# DCO.net
KiCad netlist of a schematic drawn in EAGLE
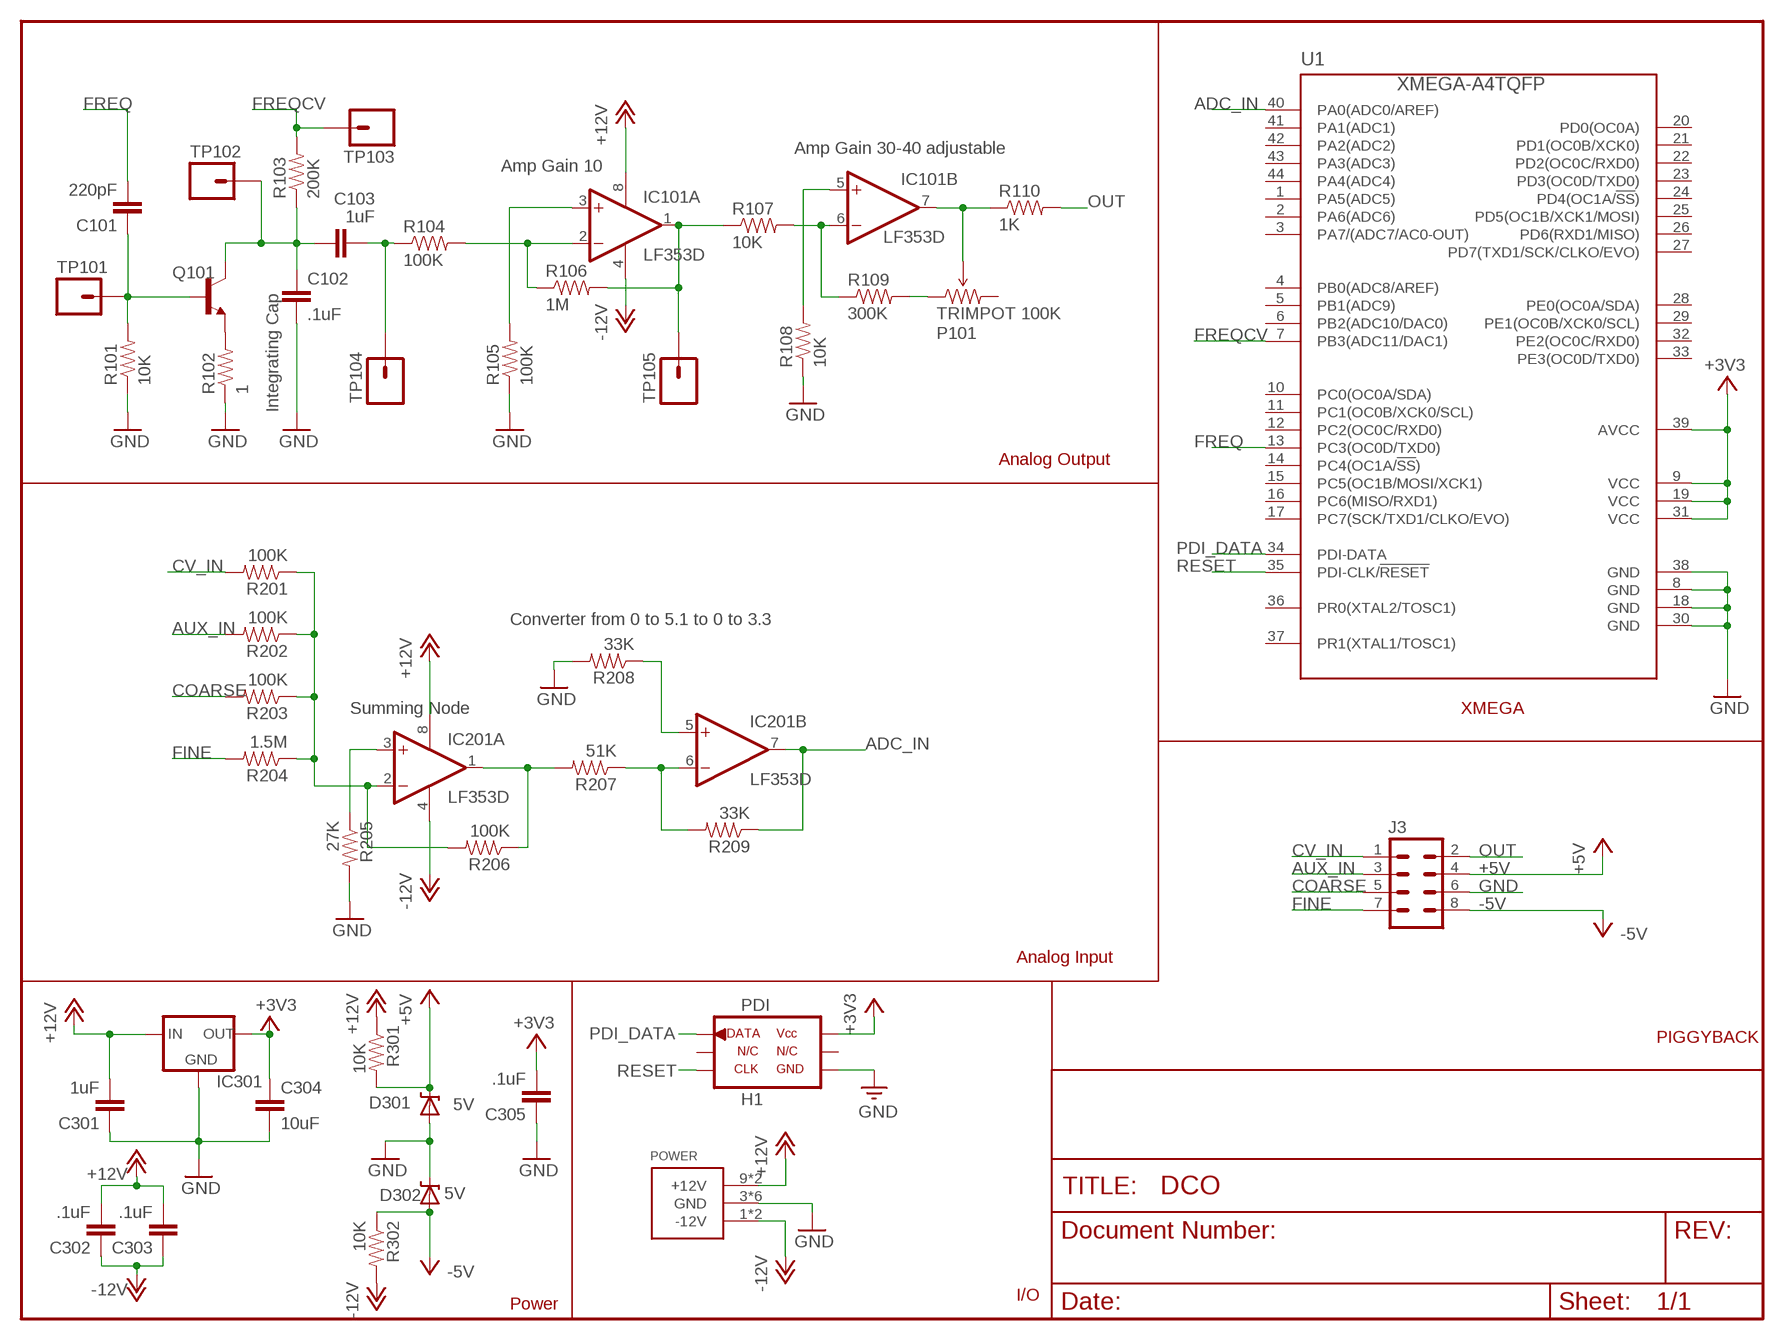
[diagram p0: schematic, sheet 1]

(export (version "E")
  (design (tool "Eeschema 10.0.6"))
  (components
    (comp (ref "C101")
      (value "220pF")
      (footprint "eagle-import:0603-CAP")
      (libsource (lib "eagle-import") (part "CAP0603-CAP"))
    )
    (comp (ref "C102")
      (value ".1uF")
      (footprint "eagle-import:1210")
      (libsource (lib "eagle-import") (part "CAP1210"))
    )
    (comp (ref "C103")
      (value "1uF")
      (footprint "eagle-import:0805")
      (libsource (lib "eagle-import") (part "CAP0805"))
    )
    (comp (ref "C301")
      (value "1uF")
      (footprint "eagle-import:0805")
      (libsource (lib "eagle-import") (part "CAP0805"))
    )
    (comp (ref "C302")
      (value ".1uF")
      (footprint "eagle-import:0603-CAP")
      (libsource (lib "eagle-import") (part "CAP0603-CAP"))
    )
    (comp (ref "C303")
      (value ".1uF")
      (footprint "eagle-import:0603-CAP")
      (libsource (lib "eagle-import") (part "CAP0603-CAP"))
    )
    (comp (ref "C304")
      (value "10uF")
      (footprint "eagle-import:1206")
      (libsource (lib "eagle-import") (part "CAP1206"))
    )
    (comp (ref "C305")
      (value ".1uF")
      (footprint "eagle-import:0603-CAP")
      (libsource (lib "eagle-import") (part "CAP0603-CAP"))
    )
    (comp (ref "D301")
      (value "5V")
      (footprint "eagle-import:SOD-323")
      (libsource (lib "eagle-import") (part "DIODE-ZENER-BZT52"))
    )
    (comp (ref "D302")
      (value "5V")
      (footprint "eagle-import:SOD-323")
      (libsource (lib "eagle-import") (part "DIODE-ZENER-BZT52"))
    )
    (comp (ref "H1")
      (value "PDI")
      (footprint "eagle-import:AVR_ISP_6")
      (libsource (lib "eagle-import") (part "AVR_PDI_6"))
    )
    (comp (ref "IC101")
      (value "LF353D")
      (footprint "eagle-import:SO08")
      (libsource (lib "eagle-import") (part "LF353D"))
    )
    (comp (ref "IC201")
      (value "LF353D")
      (footprint "eagle-import:SO08")
      (libsource (lib "eagle-import") (part "LF353D"))
    )
    (comp (ref "IC301")
      (value "V_REG_MIC2920")
      (footprint "eagle-import:SOT223")
      (libsource (lib "eagle-import") (part "V_REG_MIC2920"))
    )
    (comp (ref "J3")
      (value "M04X2")
      (footprint "eagle-import:2X4")
      (libsource (lib "eagle-import") (part "M04X2"))
    )
    (comp (ref "P101")
      (value "TRIMPOT 100K")
      (footprint "eagle-import:TRIM_POT_PTH")
      (libsource (lib "eagle-import") (part "TRIMPOTPTH"))
    )
    (comp (ref "POWER")
      (value "POWER_SIMPLE16")
      (footprint "eagle-import:POWER_16")
      (libsource (lib "eagle-import") (part "POWER_SIMPLE16"))
    )
    (comp (ref "Q101")
      (value "TRANSISTOR_NPNSOT23")
      (footprint "eagle-import:SOT23")
      (libsource (lib "eagle-import") (part "TRANSISTOR_NPNSOT23"))
    )
    (comp (ref "R101")
      (value "10K")
      (footprint "eagle-import:0603-RES")
      (libsource (lib "eagle-import") (part "RESISTOR0603-RES"))
    )
    (comp (ref "R102")
      (value "1")
      (footprint "eagle-import:0805")
      (libsource (lib "eagle-import") (part "RESISTOR0805-RES"))
    )
    (comp (ref "R103")
      (value "200K")
      (footprint "eagle-import:0603-RES")
      (libsource (lib "eagle-import") (part "RESISTOR0603-RES"))
    )
    (comp (ref "R104")
      (value "100K")
      (footprint "eagle-import:0603-RES")
      (libsource (lib "eagle-import") (part "RESISTOR0603-RES"))
    )
    (comp (ref "R105")
      (value "100K")
      (footprint "eagle-import:0603-RES")
      (libsource (lib "eagle-import") (part "RESISTOR0603-RES"))
    )
    (comp (ref "R106")
      (value "1M")
      (footprint "eagle-import:0603-RES")
      (libsource (lib "eagle-import") (part "RESISTOR0603-RES"))
    )
    (comp (ref "R107")
      (value "10K")
      (footprint "eagle-import:0603-RES")
      (libsource (lib "eagle-import") (part "RESISTOR0603-RES"))
    )
    (comp (ref "R108")
      (value "10K")
      (footprint "eagle-import:0603-RES")
      (libsource (lib "eagle-import") (part "RESISTOR0603-RES"))
    )
    (comp (ref "R109")
      (value "300K")
      (footprint "eagle-import:0603-RES")
      (libsource (lib "eagle-import") (part "RESISTOR0603-RES"))
    )
    (comp (ref "R110")
      (value "1K")
      (footprint "eagle-import:0603-RES")
      (libsource (lib "eagle-import") (part "RESISTOR0603-RES"))
    )
    (comp (ref "R201")
      (value "100K")
      (footprint "eagle-import:0603-RES")
      (libsource (lib "eagle-import") (part "RESISTOR0603-RES"))
    )
    (comp (ref "R202")
      (value "100K")
      (footprint "eagle-import:0603-RES")
      (libsource (lib "eagle-import") (part "RESISTOR0603-RES"))
    )
    (comp (ref "R203")
      (value "100K")
      (footprint "eagle-import:0603-RES")
      (libsource (lib "eagle-import") (part "RESISTOR0603-RES"))
    )
    (comp (ref "R204")
      (value "1.5M")
      (footprint "eagle-import:0603-RES")
      (libsource (lib "eagle-import") (part "RESISTOR0603-RES"))
    )
    (comp (ref "R205")
      (value "27K")
      (footprint "eagle-import:0603-RES")
      (libsource (lib "eagle-import") (part "RESISTOR0603-RES"))
    )
    (comp (ref "R206")
      (value "100K")
      (footprint "eagle-import:0603-RES")
      (libsource (lib "eagle-import") (part "RESISTOR0603-RES"))
    )
    (comp (ref "R207")
      (value "51K")
      (footprint "eagle-import:0603-RES")
      (libsource (lib "eagle-import") (part "RESISTOR0603-RES"))
    )
    (comp (ref "R208")
      (value "33K")
      (footprint "eagle-import:0603-RES")
      (libsource (lib "eagle-import") (part "RESISTOR0603-RES"))
    )
    (comp (ref "R209")
      (value "33K")
      (footprint "eagle-import:0603-RES")
      (libsource (lib "eagle-import") (part "RESISTOR0603-RES"))
    )
    (comp (ref "R301")
      (value "10K")
      (footprint "eagle-import:0603-RES")
      (libsource (lib "eagle-import") (part "RESISTOR0603-RES"))
    )
    (comp (ref "R302")
      (value "10K")
      (footprint "eagle-import:0603-RES")
      (libsource (lib "eagle-import") (part "RESISTOR0603-RES"))
    )
    (comp (ref "TP101")
      (value "M01PTH")
      (footprint "eagle-import:1X01")
      (libsource (lib "eagle-import") (part "M01PTH"))
    )
    (comp (ref "TP102")
      (value "M01PTH")
      (footprint "eagle-import:1X01")
      (libsource (lib "eagle-import") (part "M01PTH"))
    )
    (comp (ref "TP103")
      (value "M01PTH")
      (footprint "eagle-import:1X01")
      (libsource (lib "eagle-import") (part "M01PTH"))
    )
    (comp (ref "TP104")
      (value "M01PTH")
      (footprint "eagle-import:1X01")
      (libsource (lib "eagle-import") (part "M01PTH"))
    )
    (comp (ref "TP105")
      (value "M01PTH")
      (footprint "eagle-import:1X01")
      (libsource (lib "eagle-import") (part "M01PTH"))
    )
    (comp (ref "U1")
      (value "XMEGA-A4TQFP")
      (footprint "eagle-import:TQFP44")
      (libsource (lib "eagle-import") (part "XMEGA-A4TQFP"))
    )
  )
  (nets
    (net (code "1") (name "+3V3") (class "Default")
      (node (ref "C304") (pin "1") (pinfunction "1_1") (pintype "passive"))
      (node (ref "C305") (pin "2") (pinfunction "2_2") (pintype "passive"))
      (node (ref "H1") (pin "P$2") (pinfunction "VCC_IO_P$2") (pintype "passive"))
      (node (ref "IC301") (pin "3") (pinfunction "OUT_3") (pintype "output"))
      (node (ref "U1") (pin "19") (pinfunction "VCC_19") (pintype "power_in"))
      (node (ref "U1") (pin "31") (pinfunction "VCC_31") (pintype "power_in"))
      (node (ref "U1") (pin "39") (pinfunction "AVCC_39") (pintype "power_in"))
      (node (ref "U1") (pin "9") (pinfunction "VCC_9") (pintype "power_in"))
    )
    (net (code "2") (name "+5V") (class "Default")
      (node (ref "D301") (pin "1") (pinfunction "C_1") (pintype "passive"))
      (node (ref "J3") (pin "4") (pinfunction "4_4") (pintype "passive"))
      (node (ref "R301") (pin "2") (pinfunction "2_2") (pintype "passive"))
    )
    (net (code "3") (name "+12V") (class "Default")
      (node (ref "C301") (pin "2") (pinfunction "2_2") (pintype "passive"))
      (node (ref "C302") (pin "2") (pinfunction "2_2") (pintype "passive"))
      (node (ref "C303") (pin "2") (pinfunction "2_2") (pintype "passive"))
      (node (ref "IC101") (pin "8") (pinfunction "V+_8") (pintype "power_in"))
      (node (ref "IC201") (pin "8") (pinfunction "V+_8") (pintype "power_in"))
      (node (ref "IC301") (pin "1") (pinfunction "IN_1") (pintype "input"))
      (node (ref "POWER") (pin "10") (pinfunction "+12V_10") (pintype "bidirectional"))
      (node (ref "POWER") (pin "9") (pinfunction "+12V_9") (pintype "bidirectional"))
      (node (ref "R301") (pin "1") (pinfunction "1_1") (pintype "passive"))
    )
    (net (code "4") (name "-5V") (class "Default")
      (node (ref "D302") (pin "2") (pinfunction "A_2") (pintype "passive"))
      (node (ref "J3") (pin "8") (pinfunction "8_8") (pintype "passive"))
      (node (ref "R302") (pin "1") (pinfunction "1_1") (pintype "passive"))
    )
    (net (code "5") (name "-12V") (class "Default")
      (node (ref "C302") (pin "1") (pinfunction "1_1") (pintype "passive"))
      (node (ref "C303") (pin "1") (pinfunction "1_1") (pintype "passive"))
      (node (ref "IC101") (pin "4") (pinfunction "V-_4") (pintype "power_in"))
      (node (ref "IC201") (pin "4") (pinfunction "V-_4") (pintype "power_in"))
      (node (ref "POWER") (pin "1") (pinfunction "-12V_1") (pintype "bidirectional"))
      (node (ref "POWER") (pin "2") (pinfunction "-12V_2") (pintype "bidirectional"))
      (node (ref "R302") (pin "2") (pinfunction "2_2") (pintype "passive"))
    )
    (net (code "6") (name "/ADC_IN") (class "Default")
      (node (ref "IC201") (pin "7") (pinfunction "OUT_7") (pintype "output"))
      (node (ref "R209") (pin "1") (pinfunction "1_1") (pintype "passive"))
      (node (ref "U1") (pin "40") (pinfunction "PA0(ADC0/AREF)_40") (pintype "bidirectional"))
    )
    (net (code "7") (name "/AUX_IN") (class "Default")
      (node (ref "J3") (pin "3") (pinfunction "3_3") (pintype "passive"))
      (node (ref "R202") (pin "2") (pinfunction "2_2") (pintype "passive"))
    )
    (net (code "8") (name "/COARSE") (class "Default")
      (node (ref "J3") (pin "5") (pinfunction "5_5") (pintype "passive"))
      (node (ref "R203") (pin "2") (pinfunction "2_2") (pintype "passive"))
    )
    (net (code "9") (name "/CV_IN") (class "Default")
      (node (ref "J3") (pin "1") (pinfunction "1_1") (pintype "passive"))
      (node (ref "R201") (pin "2") (pinfunction "2_2") (pintype "passive"))
    )
    (net (code "10") (name "/FINE") (class "Default")
      (node (ref "J3") (pin "7") (pinfunction "7_7") (pintype "passive"))
      (node (ref "R204") (pin "2") (pinfunction "2_2") (pintype "passive"))
    )
    (net (code "11") (name "/FREQ") (class "Default")
      (node (ref "C101") (pin "2") (pinfunction "2_2") (pintype "passive"))
      (node (ref "U1") (pin "13") (pinfunction "PC3(OC0D/TXD0)_13") (pintype "bidirectional"))
    )
    (net (code "12") (name "/FREQCV") (class "Default")
      (node (ref "R103") (pin "2") (pinfunction "2_2") (pintype "passive"))
      (node (ref "TP103") (pin "1") (pinfunction "1_1") (pintype "passive"))
      (node (ref "U1") (pin "7") (pinfunction "PB3(ADC11/DAC1)_7") (pintype "bidirectional"))
    )
    (net (code "13") (name "/OUT") (class "Default")
      (node (ref "J3") (pin "2") (pinfunction "2_2") (pintype "passive"))
      (node (ref "R110") (pin "2") (pinfunction "2_2") (pintype "passive"))
    )
    (net (code "14") (name "/PDI_DATA") (class "Default")
      (node (ref "H1") (pin "P$1") (pinfunction "DATA_P$1") (pintype "passive"))
      (node (ref "U1") (pin "34") (pinfunction "PDI-DATA_34") (pintype "bidirectional"))
    )
    (net (code "15") (name "/RESET") (class "Default")
      (node (ref "H1") (pin "P$5") (pinfunction "CLK_P$5") (pintype "passive"))
      (node (ref "U1") (pin "35") (pinfunction "PDI-CLK/~{RESET}_35") (pintype "input"))
    )
    (net (code "16") (name "GND") (class "Default")
      (node (ref "C102") (pin "2") (pinfunction "2_2") (pintype "passive"))
      (node (ref "C301") (pin "1") (pinfunction "1_1") (pintype "passive"))
      (node (ref "C304") (pin "2") (pinfunction "2_2") (pintype "passive"))
      (node (ref "C305") (pin "1") (pinfunction "1_1") (pintype "passive"))
      (node (ref "D301") (pin "2") (pinfunction "A_2") (pintype "passive"))
      (node (ref "D302") (pin "1") (pinfunction "C_1") (pintype "passive"))
      (node (ref "H1") (pin "P$6") (pinfunction "GND_P$6") (pintype "passive"))
      (node (ref "IC301") (pin "2") (pinfunction "GND_2") (pintype "input"))
      (node (ref "J3") (pin "6") (pinfunction "6_6") (pintype "passive"))
      (node (ref "POWER") (pin "3") (pinfunction "GND_3") (pintype "bidirectional"))
      (node (ref "POWER") (pin "4") (pinfunction "GND_4") (pintype "bidirectional"))
      (node (ref "POWER") (pin "5") (pinfunction "GND_5") (pintype "bidirectional"))
      (node (ref "POWER") (pin "6") (pinfunction "GND_6") (pintype "bidirectional"))
      (node (ref "POWER") (pin "7") (pinfunction "GND_7") (pintype "bidirectional"))
      (node (ref "POWER") (pin "8") (pinfunction "GND_8") (pintype "bidirectional"))
      (node (ref "R101") (pin "1") (pinfunction "1_1") (pintype "passive"))
      (node (ref "R102") (pin "1") (pinfunction "1_1") (pintype "passive"))
      (node (ref "R105") (pin "1") (pinfunction "1_1") (pintype "passive"))
      (node (ref "R108") (pin "1") (pinfunction "1_1") (pintype "passive"))
      (node (ref "R205") (pin "2") (pinfunction "2_2") (pintype "passive"))
      (node (ref "R208") (pin "2") (pinfunction "2_2") (pintype "passive"))
      (node (ref "U1") (pin "18") (pinfunction "GND_18") (pintype "power_in"))
      (node (ref "U1") (pin "30") (pinfunction "GND_30") (pintype "power_in"))
      (node (ref "U1") (pin "38") (pinfunction "GND_38") (pintype "power_in"))
      (node (ref "U1") (pin "8") (pinfunction "GND_8") (pintype "power_in"))
    )
    (net (code "17") (name "Net-(C103-Pad2)") (class "Default")
      (node (ref "C103") (pin "2") (pinfunction "2_2") (pintype "passive"))
      (node (ref "R104") (pin "1") (pinfunction "1_1") (pintype "passive"))
      (node (ref "TP104") (pin "1") (pinfunction "1_1") (pintype "passive"))
    )
    (net (code "18") (name "Net-(IC101A-+IN)") (class "Default")
      (node (ref "IC101") (pin "3") (pinfunction "+IN_3") (pintype "input"))
      (node (ref "R105") (pin "2") (pinfunction "2_2") (pintype "passive"))
    )
    (net (code "19") (name "Net-(IC101A--IN)") (class "Default")
      (node (ref "IC101") (pin "2") (pinfunction "-IN_2") (pintype "input"))
      (node (ref "R104") (pin "2") (pinfunction "2_2") (pintype "passive"))
      (node (ref "R106") (pin "1") (pinfunction "1_1") (pintype "passive"))
    )
    (net (code "20") (name "Net-(IC101A-OUT)") (class "Default")
      (node (ref "IC101") (pin "1") (pinfunction "OUT_1") (pintype "output"))
      (node (ref "R106") (pin "2") (pinfunction "2_2") (pintype "passive"))
      (node (ref "R107") (pin "1") (pinfunction "1_1") (pintype "passive"))
      (node (ref "TP105") (pin "1") (pinfunction "1_1") (pintype "passive"))
    )
    (net (code "21") (name "Net-(IC101B-+IN)") (class "Default")
      (node (ref "IC101") (pin "5") (pinfunction "+IN_5") (pintype "input"))
      (node (ref "R108") (pin "2") (pinfunction "2_2") (pintype "passive"))
    )
    (net (code "22") (name "Net-(IC101B--IN)") (class "Default")
      (node (ref "IC101") (pin "6") (pinfunction "-IN_6") (pintype "input"))
      (node (ref "R107") (pin "2") (pinfunction "2_2") (pintype "passive"))
      (node (ref "R109") (pin "1") (pinfunction "1_1") (pintype "passive"))
    )
    (net (code "23") (name "Net-(IC101B-OUT)") (class "Default")
      (node (ref "IC101") (pin "7") (pinfunction "OUT_7") (pintype "output"))
      (node (ref "P101") (pin "2") (pinfunction "WIPER_2") (pintype "passive"))
      (node (ref "R110") (pin "1") (pinfunction "1_1") (pintype "passive"))
    )
    (net (code "24") (name "Net-(IC201A-+IN)") (class "Default")
      (node (ref "IC201") (pin "3") (pinfunction "+IN_3") (pintype "input"))
      (node (ref "R205") (pin "1") (pinfunction "1_1") (pintype "passive"))
    )
    (net (code "25") (name "Net-(IC201A--IN)") (class "Default")
      (node (ref "IC201") (pin "2") (pinfunction "-IN_2") (pintype "input"))
      (node (ref "R201") (pin "1") (pinfunction "1_1") (pintype "passive"))
      (node (ref "R202") (pin "1") (pinfunction "1_1") (pintype "passive"))
      (node (ref "R203") (pin "1") (pinfunction "1_1") (pintype "passive"))
      (node (ref "R204") (pin "1") (pinfunction "1_1") (pintype "passive"))
      (node (ref "R206") (pin "2") (pinfunction "2_2") (pintype "passive"))
    )
    (net (code "26") (name "Net-(IC201A-OUT)") (class "Default")
      (node (ref "IC201") (pin "1") (pinfunction "OUT_1") (pintype "output"))
      (node (ref "R206") (pin "1") (pinfunction "1_1") (pintype "passive"))
      (node (ref "R207") (pin "2") (pinfunction "2_2") (pintype "passive"))
    )
    (net (code "27") (name "Net-(IC201B-+IN)") (class "Default")
      (node (ref "IC201") (pin "5") (pinfunction "+IN_5") (pintype "input"))
      (node (ref "R208") (pin "1") (pinfunction "1_1") (pintype "passive"))
    )
    (net (code "28") (name "Net-(IC201B--IN)") (class "Default")
      (node (ref "IC201") (pin "6") (pinfunction "-IN_6") (pintype "input"))
      (node (ref "R207") (pin "1") (pinfunction "1_1") (pintype "passive"))
      (node (ref "R209") (pin "2") (pinfunction "2_2") (pintype "passive"))
    )
    (net (code "29") (name "Net-(P101-CCW)") (class "Default")
      (node (ref "P101") (pin "1") (pinfunction "CCW_1") (pintype "passive"))
      (node (ref "R109") (pin "2") (pinfunction "2_2") (pintype "passive"))
    )
    (net (code "30") (name "Net-(Q101-B)") (class "Default")
      (node (ref "C101") (pin "1") (pinfunction "1_1") (pintype "passive"))
      (node (ref "Q101") (pin "1") (pinfunction "B_1") (pintype "passive"))
      (node (ref "R101") (pin "2") (pinfunction "2_2") (pintype "passive"))
      (node (ref "TP101") (pin "1") (pinfunction "1_1") (pintype "passive"))
    )
    (net (code "31") (name "Net-(Q101-C)") (class "Default")
      (node (ref "C102") (pin "1") (pinfunction "1_1") (pintype "passive"))
      (node (ref "C103") (pin "1") (pinfunction "1_1") (pintype "passive"))
      (node (ref "Q101") (pin "3") (pinfunction "C_3") (pintype "passive"))
      (node (ref "R103") (pin "1") (pinfunction "1_1") (pintype "passive"))
      (node (ref "TP102") (pin "1") (pinfunction "1_1") (pintype "passive"))
    )
    (net (code "32") (name "Net-(Q101-E)") (class "Default")
      (node (ref "Q101") (pin "2") (pinfunction "E_2") (pintype "passive"))
      (node (ref "R102") (pin "2") (pinfunction "2_2") (pintype "passive"))
    )
    (net (code "33") (name "unconnected-(H1-NC1-PadP$3)") (class "Default")
      (node (ref "H1") (pin "P$3") (pinfunction "NC1_P$3") (pintype "passive"))
    )
    (net (code "34") (name "unconnected-(H1-NC2-PadP$4)") (class "Default")
      (node (ref "H1") (pin "P$4") (pinfunction "NC2_P$4") (pintype "passive"))
    )
    (net (code "35") (name "unconnected-(P101-CW-Pad3)") (class "Default")
      (node (ref "P101") (pin "3") (pinfunction "CW_3") (pintype "passive"))
    )
    (net (code "36") (name "unconnected-(U1-PA1(ADC1)-Pad41)") (class "Default")
      (node (ref "U1") (pin "41") (pinfunction "PA1(ADC1)_41") (pintype "bidirectional"))
    )
    (net (code "37") (name "unconnected-(U1-PA2(ADC2)-Pad42)") (class "Default")
      (node (ref "U1") (pin "42") (pinfunction "PA2(ADC2)_42") (pintype "bidirectional"))
    )
    (net (code "38") (name "unconnected-(U1-PA3(ADC3)-Pad43)") (class "Default")
      (node (ref "U1") (pin "43") (pinfunction "PA3(ADC3)_43") (pintype "bidirectional"))
    )
    (net (code "39") (name "unconnected-(U1-PA4(ADC4)-Pad44)") (class "Default")
      (node (ref "U1") (pin "44") (pinfunction "PA4(ADC4)_44") (pintype "bidirectional"))
    )
    (net (code "40") (name "unconnected-(U1-PA5(ADC5)-Pad1)") (class "Default")
      (node (ref "U1") (pin "1") (pinfunction "PA5(ADC5)_1") (pintype "bidirectional"))
    )
    (net (code "41") (name "unconnected-(U1-PA6(ADC6)-Pad2)") (class "Default")
      (node (ref "U1") (pin "2") (pinfunction "PA6(ADC6)_2") (pintype "bidirectional"))
    )
    (net (code "42") (name "unconnected-(U1-PA7{slash}(ADC7{slash}AC0-OUT)-Pad3)") (class "Default")
      (node (ref "U1") (pin "3") (pinfunction "PA7/(ADC7/AC0-OUT)_3") (pintype "bidirectional"))
    )
    (net (code "43") (name "unconnected-(U1-PB0(ADC8{slash}AREF)-Pad4)") (class "Default")
      (node (ref "U1") (pin "4") (pinfunction "PB0(ADC8/AREF)_4") (pintype "bidirectional"))
    )
    (net (code "44") (name "unconnected-(U1-PB1(ADC9)-Pad5)") (class "Default")
      (node (ref "U1") (pin "5") (pinfunction "PB1(ADC9)_5") (pintype "bidirectional"))
    )
    (net (code "45") (name "unconnected-(U1-PB2(ADC10{slash}DAC0)-Pad6)") (class "Default")
      (node (ref "U1") (pin "6") (pinfunction "PB2(ADC10/DAC0)_6") (pintype "bidirectional"))
    )
    (net (code "46") (name "unconnected-(U1-PC0(OC0A{slash}SDA)-Pad10)") (class "Default")
      (node (ref "U1") (pin "10") (pinfunction "PC0(OC0A/SDA)_10") (pintype "bidirectional"))
    )
    (net (code "47") (name "unconnected-(U1-PC1(OC0B{slash}XCK0{slash}SCL)-Pad11)") (class "Default")
      (node (ref "U1") (pin "11") (pinfunction "PC1(OC0B/XCK0/SCL)_11") (pintype "bidirectional"))
    )
    (net (code "48") (name "unconnected-(U1-PC2(OC0C{slash}RXD0)-Pad12)") (class "Default")
      (node (ref "U1") (pin "12") (pinfunction "PC2(OC0C/RXD0)_12") (pintype "bidirectional"))
    )
    (net (code "49") (name "unconnected-(U1-PC4(OC1A{slash}~{SS})-Pad14)") (class "Default")
      (node (ref "U1") (pin "14") (pinfunction "PC4(OC1A/~{SS})_14") (pintype "bidirectional"))
    )
    (net (code "50") (name "unconnected-(U1-PC5(OC1B{slash}MOSI{slash}XCK1)-Pad15)") (class "Default")
      (node (ref "U1") (pin "15") (pinfunction "PC5(OC1B/MOSI/XCK1)_15") (pintype "bidirectional"))
    )
    (net (code "51") (name "unconnected-(U1-PC6(MISO{slash}RXD1)-Pad16)") (class "Default")
      (node (ref "U1") (pin "16") (pinfunction "PC6(MISO/RXD1)_16") (pintype "bidirectional"))
    )
    (net (code "52") (name "unconnected-(U1-PC7(SCK{slash}TXD1{slash}CLKO{slash}EVO)-Pad17)") (class "Default")
      (node (ref "U1") (pin "17") (pinfunction "PC7(SCK/TXD1/CLKO/EVO)_17") (pintype "bidirectional"))
    )
    (net (code "53") (name "unconnected-(U1-PD0(OC0A)-Pad20)") (class "Default")
      (node (ref "U1") (pin "20") (pinfunction "PD0(OC0A)_20") (pintype "bidirectional"))
    )
    (net (code "54") (name "unconnected-(U1-PD1(OC0B{slash}XCK0)-Pad21)") (class "Default")
      (node (ref "U1") (pin "21") (pinfunction "PD1(OC0B/XCK0)_21") (pintype "bidirectional"))
    )
    (net (code "55") (name "unconnected-(U1-PD2(OC0C{slash}RXD0)-Pad22)") (class "Default")
      (node (ref "U1") (pin "22") (pinfunction "PD2(OC0C/RXD0)_22") (pintype "bidirectional"))
    )
    (net (code "56") (name "unconnected-(U1-PD3(OC0D{slash}TXD0)-Pad23)") (class "Default")
      (node (ref "U1") (pin "23") (pinfunction "PD3(OC0D/TXD0)_23") (pintype "bidirectional"))
    )
    (net (code "57") (name "unconnected-(U1-PD4(OC1A{slash}~{SS})-Pad24)") (class "Default")
      (node (ref "U1") (pin "24") (pinfunction "PD4(OC1A/~{SS})_24") (pintype "bidirectional"))
    )
    (net (code "58") (name "unconnected-(U1-PD5(OC1B{slash}XCK1{slash}MOSI)-Pad25)") (class "Default")
      (node (ref "U1") (pin "25") (pinfunction "PD5(OC1B/XCK1/MOSI)_25") (pintype "bidirectional"))
    )
    (net (code "59") (name "unconnected-(U1-PD6(RXD1{slash}MISO)-Pad26)") (class "Default")
      (node (ref "U1") (pin "26") (pinfunction "PD6(RXD1/MISO)_26") (pintype "bidirectional"))
    )
    (net (code "60") (name "unconnected-(U1-PD7(TXD1{slash}SCK{slash}CLKO{slash}EVO)-Pad27)") (class "Default")
      (node (ref "U1") (pin "27") (pinfunction "PD7(TXD1/SCK/CLKO/EVO)_27") (pintype "bidirectional"))
    )
    (net (code "61") (name "unconnected-(U1-PE0(OC0A{slash}SDA)-Pad28)") (class "Default")
      (node (ref "U1") (pin "28") (pinfunction "PE0(OC0A/SDA)_28") (pintype "bidirectional"))
    )
    (net (code "62") (name "unconnected-(U1-PE1(OC0B{slash}XCK0{slash}SCL)-Pad29)") (class "Default")
      (node (ref "U1") (pin "29") (pinfunction "PE1(OC0B/XCK0/SCL)_29") (pintype "bidirectional"))
    )
    (net (code "63") (name "unconnected-(U1-PE2(OC0C{slash}RXD0)-Pad32)") (class "Default")
      (node (ref "U1") (pin "32") (pinfunction "PE2(OC0C/RXD0)_32") (pintype "bidirectional"))
    )
    (net (code "64") (name "unconnected-(U1-PE3(OC0D{slash}TXD0)-Pad33)") (class "Default")
      (node (ref "U1") (pin "33") (pinfunction "PE3(OC0D/TXD0)_33") (pintype "bidirectional"))
    )
    (net (code "65") (name "unconnected-(U1-PR0(XTAL2{slash}TOSC1)-Pad36)") (class "Default")
      (node (ref "U1") (pin "36") (pinfunction "PR0(XTAL2/TOSC1)_36") (pintype "bidirectional"))
    )
    (net (code "66") (name "unconnected-(U1-PR1(XTAL1{slash}TOSC1)-Pad37)") (class "Default")
      (node (ref "U1") (pin "37") (pinfunction "PR1(XTAL1/TOSC1)_37") (pintype "bidirectional"))
    )
  )
)
